# source_eagle.net
KiCad netlist of a schematic drawn in EAGLE
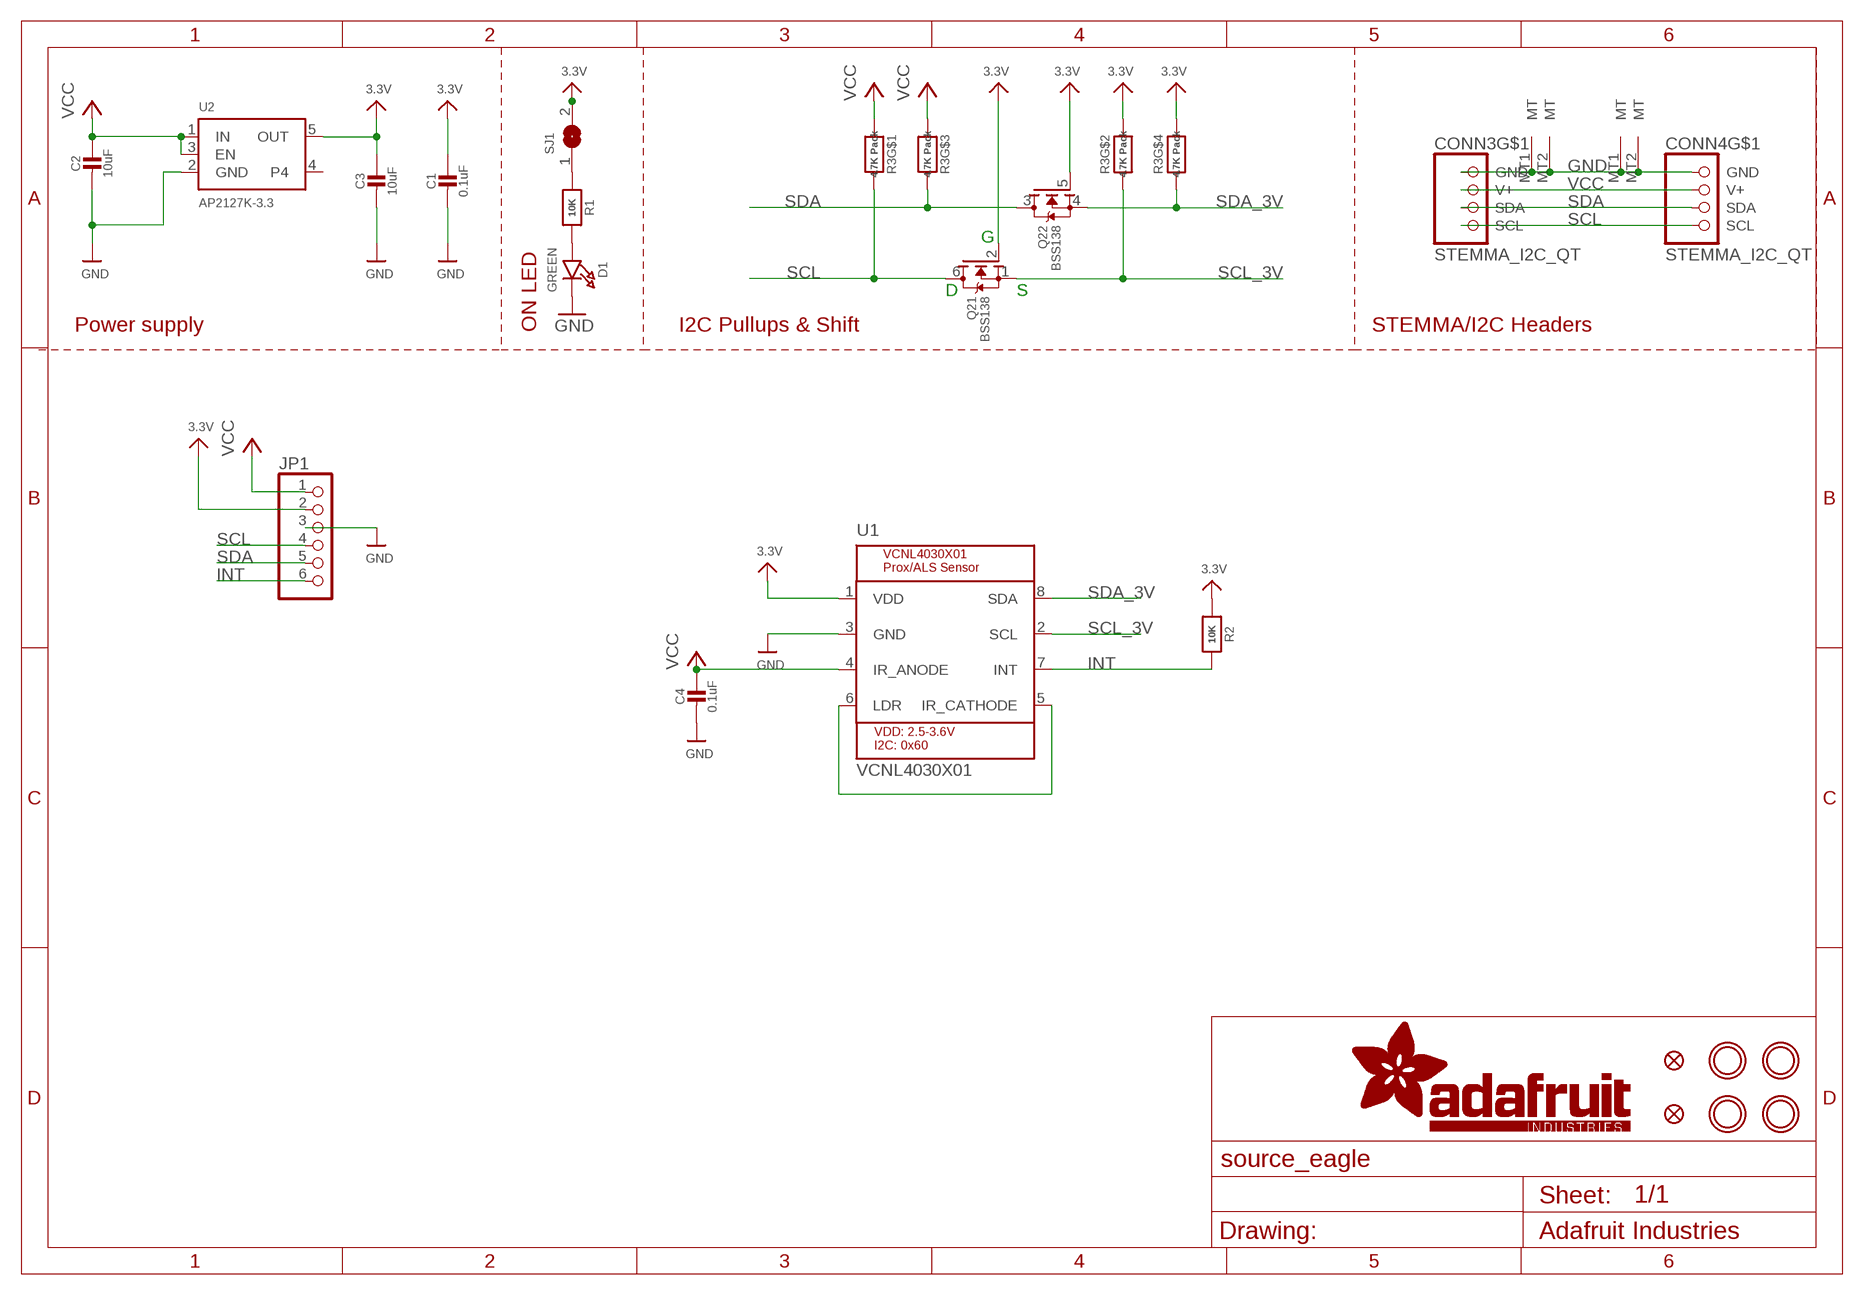
[diagram p0: schematic, sheet 1]

(export (version "E")
  (design (tool "Eeschema 10.0.6"))
  (components
    (comp (ref "C1")
      (value "0.1uF")
      (footprint "eagle-import:0603-NO")
      (libsource (lib "eagle-import") (part "CAP_CERAMIC0603_NO"))
    )
    (comp (ref "C2")
      (value "10uF")
      (footprint "eagle-import:0805-NO")
      (libsource (lib "eagle-import") (part "CAP_CERAMIC0805-NOOUTLINE"))
    )
    (comp (ref "C3")
      (value "10uF")
      (footprint "eagle-import:0805-NO")
      (libsource (lib "eagle-import") (part "CAP_CERAMIC0805-NOOUTLINE"))
    )
    (comp (ref "C4")
      (value "0.1uF")
      (footprint "eagle-import:0603-NO")
      (libsource (lib "eagle-import") (part "CAP_CERAMIC0603_NO"))
    )
    (comp (ref "CONN3")
      (value "STEMMA_I2C_QT")
      (footprint "eagle-import:JST_SH4")
      (libsource (lib "eagle-import") (part "STEMMA_I2C_QT"))
    )
    (comp (ref "CONN4")
      (value "STEMMA_I2C_QT")
      (footprint "eagle-import:JST_SH4")
      (libsource (lib "eagle-import") (part "STEMMA_I2C_QT"))
    )
    (comp (ref "D1")
      (value "GREEN")
      (footprint "eagle-import:CHIPLED_0603_NOOUTLINE")
      (libsource (lib "eagle-import") (part "LED0603_NOOUTLINE"))
    )
    (comp (ref "FID3")
      (value "FIDUCIAL_0.5MM")
      (footprint "eagle-import:FIDUCIAL_0.5MM")
      (libsource (lib "eagle-import") (part "FIDUCIAL_0.5MM"))
    )
    (comp (ref "FID4")
      (value "FIDUCIAL_0.5MM")
      (footprint "eagle-import:FIDUCIAL_0.5MM")
      (libsource (lib "eagle-import") (part "FIDUCIAL_0.5MM"))
    )
    (comp (ref "JP1")
      (value "HEADER-1X670MIL")
      (footprint "eagle-import:1X06_ROUND_70")
      (libsource (lib "eagle-import") (part "HEADER-1X670MIL"))
    )
    (comp (ref "Q2")
      (value "BSS138")
      (footprint "eagle-import:SOT363")
      (libsource (lib "eagle-import") (part "MOSFET-N_DUAL"))
    )
    (comp (ref "R1")
      (value "10K")
      (footprint "eagle-import:0603-NO")
      (libsource (lib "eagle-import") (part "RESISTOR_0603_NOOUT"))
    )
    (comp (ref "R2")
      (value "10K")
      (footprint "eagle-import:0603-NO")
      (libsource (lib "eagle-import") (part "RESISTOR_0603_NOOUT"))
    )
    (comp (ref "R3")
      (value "4.7K Pack")
      (footprint "eagle-import:RESPACK_4X0603")
      (libsource (lib "eagle-import") (part "RESISTOR_4PACK"))
    )
    (comp (ref "SJ1")
      (value "SOLDERJUMPERCLOSED")
      (footprint "eagle-import:SOLDERJUMPER_CLOSEDWIRE")
      (libsource (lib "eagle-import") (part "SOLDERJUMPERCLOSED"))
    )
    (comp (ref "U$1")
      (value "MOUNTINGHOLE2.5")
      (footprint "eagle-import:MOUNTINGHOLE_2.5_PLATED")
      (libsource (lib "eagle-import") (part "MOUNTINGHOLE2.5"))
    )
    (comp (ref "U$17")
      (value "MOUNTINGHOLE2.5")
      (footprint "eagle-import:MOUNTINGHOLE_2.5_PLATED")
      (libsource (lib "eagle-import") (part "MOUNTINGHOLE2.5"))
    )
    (comp (ref "U$19")
      (value "MOUNTINGHOLE2.5")
      (footprint "eagle-import:MOUNTINGHOLE_2.5_PLATED")
      (libsource (lib "eagle-import") (part "MOUNTINGHOLE2.5"))
    )
    (comp (ref "U$21")
      (value "MOUNTINGHOLE2.5")
      (footprint "eagle-import:MOUNTINGHOLE_2.5_PLATED")
      (libsource (lib "eagle-import") (part "MOUNTINGHOLE2.5"))
    )
    (comp (ref "U1")
      (value "VCNL4030X01")
      (footprint "eagle-import:VISHAY_VCNL4030X01")
      (fields (field (name "MF") "Vishay") (field (name "MP") "VCNL4030X01-GS08"))
      (libsource (lib "eagle-import") (part "VCNL4030X01"))
    )
    (comp (ref "U2")
      (value "AP2127K-3.3")
      (footprint "eagle-import:SOT23-5")
      (libsource (lib "eagle-import") (part "VREG_SOT23-5"))
    )
  )
  (nets
    (net (code "1") (name "/INT") (class "Default")
      (node (ref "JP1") (pin "6") (pinfunction "6_6") (pintype "passive"))
      (node (ref "R2") (pin "2") (pinfunction "2_2") (pintype "passive"))
      (node (ref "U1") (pin "7") (pinfunction "INT_7") (pintype "output"))
    )
    (net (code "2") (name "/SCL") (class "Default")
      (node (ref "CONN3") (pin "4") (pinfunction "SCL_4") (pintype "passive"))
      (node (ref "CONN4") (pin "4") (pinfunction "SCL_4") (pintype "passive"))
      (node (ref "JP1") (pin "4") (pinfunction "4_4") (pintype "passive"))
      (node (ref "Q2") (pin "6") (pinfunction "D_6") (pintype "bidirectional"))
      (node (ref "R3") (pin "8") (pinfunction "2_8") (pintype "passive"))
    )
    (net (code "3") (name "/SCL_3V") (class "Default")
      (node (ref "Q2") (pin "1") (pinfunction "S_1") (pintype "bidirectional"))
      (node (ref "R3") (pin "7") (pinfunction "2_7") (pintype "passive"))
      (node (ref "U1") (pin "2") (pinfunction "SCL_2") (pintype "input"))
    )
    (net (code "4") (name "/SDA") (class "Default")
      (node (ref "CONN3") (pin "3") (pinfunction "SDA_3") (pintype "passive"))
      (node (ref "CONN4") (pin "3") (pinfunction "SDA_3") (pintype "passive"))
      (node (ref "JP1") (pin "5") (pinfunction "5_5") (pintype "passive"))
      (node (ref "Q2") (pin "3") (pinfunction "D_3") (pintype "bidirectional"))
      (node (ref "R3") (pin "6") (pinfunction "2_6") (pintype "passive"))
    )
    (net (code "5") (name "/SDA_3V") (class "Default")
      (node (ref "Q2") (pin "4") (pinfunction "S_4") (pintype "bidirectional"))
      (node (ref "R3") (pin "5") (pinfunction "2_5") (pintype "passive"))
      (node (ref "U1") (pin "8") (pinfunction "SDA_8") (pintype "bidirectional"))
    )
    (net (code "6") (name "3.3V") (class "Default")
      (node (ref "C1") (pin "1") (pinfunction "1_1") (pintype "passive"))
      (node (ref "C3") (pin "1") (pinfunction "1_1") (pintype "passive"))
      (node (ref "JP1") (pin "2") (pinfunction "2_2") (pintype "passive"))
      (node (ref "Q2") (pin "2") (pinfunction "G_2") (pintype "bidirectional"))
      (node (ref "Q2") (pin "5") (pinfunction "G_5") (pintype "bidirectional"))
      (node (ref "R2") (pin "1") (pinfunction "1_1") (pintype "passive"))
      (node (ref "R3") (pin "2") (pinfunction "1_2") (pintype "passive"))
      (node (ref "R3") (pin "4") (pinfunction "1_4") (pintype "passive"))
      (node (ref "SJ1") (pin "2") (pinfunction "2_2") (pintype "passive"))
      (node (ref "U1") (pin "1") (pinfunction "VDD_1") (pintype "power_in"))
      (node (ref "U2") (pin "5") (pinfunction "OUT_5") (pintype "power_in"))
    )
    (net (code "7") (name "GND") (class "Default")
      (node (ref "C1") (pin "2") (pinfunction "2_2") (pintype "passive"))
      (node (ref "C2") (pin "2") (pinfunction "2_2") (pintype "passive"))
      (node (ref "C3") (pin "2") (pinfunction "2_2") (pintype "passive"))
      (node (ref "C4") (pin "2") (pinfunction "2_2") (pintype "passive"))
      (node (ref "CONN3") (pin "1") (pinfunction "GND_1") (pintype "passive"))
      (node (ref "CONN3") (pin "MT1") (pinfunction "MT_MT1") (pintype "bidirectional"))
      (node (ref "CONN3") (pin "MT2") (pinfunction "MT_MT2") (pintype "bidirectional"))
      (node (ref "CONN4") (pin "1") (pinfunction "GND_1") (pintype "passive"))
      (node (ref "CONN4") (pin "MT1") (pinfunction "MT_MT1") (pintype "bidirectional"))
      (node (ref "CONN4") (pin "MT2") (pinfunction "MT_MT2") (pintype "bidirectional"))
      (node (ref "D1") (pin "C") (pinfunction "C_C") (pintype "passive"))
      (node (ref "JP1") (pin "3") (pinfunction "3_3") (pintype "passive"))
      (node (ref "U1") (pin "3") (pinfunction "GND_3") (pintype "power_in"))
      (node (ref "U2") (pin "2") (pinfunction "GND_2") (pintype "power_in"))
    )
    (net (code "8") (name "Net-(D1-PadA)") (class "Default")
      (node (ref "D1") (pin "A") (pinfunction "A_A") (pintype "passive"))
      (node (ref "R1") (pin "2") (pinfunction "2_2") (pintype "passive"))
    )
    (net (code "9") (name "Net-(R1-Pad1)") (class "Default")
      (node (ref "R1") (pin "1") (pinfunction "1_1") (pintype "passive"))
      (node (ref "SJ1") (pin "1") (pinfunction "1_1") (pintype "passive"))
    )
    (net (code "10") (name "Net-(U1-IR_CATHODE)") (class "Default")
      (node (ref "U1") (pin "5") (pinfunction "IR_CATHODE_5") (pintype "passive"))
      (node (ref "U1") (pin "6") (pinfunction "LDR_6") (pintype "input"))
    )
    (net (code "11") (name "VCC") (class "Default")
      (node (ref "C2") (pin "1") (pinfunction "1_1") (pintype "passive"))
      (node (ref "C4") (pin "1") (pinfunction "1_1") (pintype "passive"))
      (node (ref "CONN3") (pin "2") (pinfunction "V+_2") (pintype "passive"))
      (node (ref "CONN4") (pin "2") (pinfunction "V+_2") (pintype "passive"))
      (node (ref "JP1") (pin "1") (pinfunction "1_1") (pintype "passive"))
      (node (ref "R3") (pin "1") (pinfunction "1_1") (pintype "passive"))
      (node (ref "R3") (pin "3") (pinfunction "1_3") (pintype "passive"))
      (node (ref "U1") (pin "4") (pinfunction "IR_ANODE_4") (pintype "power_in"))
      (node (ref "U2") (pin "1") (pinfunction "IN_1") (pintype "power_in"))
      (node (ref "U2") (pin "3") (pinfunction "EN_3") (pintype "input"))
    )
    (net (code "12") (name "unconnected-(U2-P4-Pad4)") (class "Default")
      (node (ref "U2") (pin "4") (pinfunction "P4_4") (pintype "bidirectional"))
    )
  )
)
